# facade.net
KiCad netlist of a schematic drawn in EAGLE
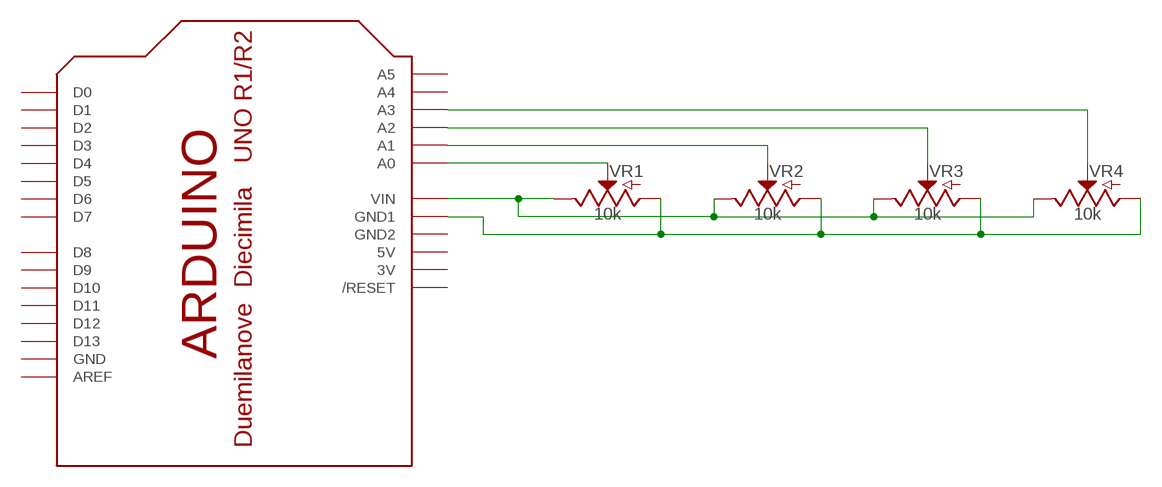
[diagram p0: schematic, sheet 1]

(export (version "E")
  (design (tool "Eeschema 10.0.6"))
  (components
    (comp (ref "U$1")
      (value "ARDUINOUNO")
      (footprint "eagle-import:ARDUINO")
      (libsource (lib "eagle-import") (part "ARDUINOUNO"))
    )
    (comp (ref "VR1")
      (value "10k")
      (footprint "eagle-import:POT-PTH-ALPS")
      (libsource (lib "eagle-import") (part "POTENTIOMETER-PTH-9MM-1/20W-20%"))
    )
    (comp (ref "VR2")
      (value "10k")
      (footprint "eagle-import:POT-PTH-ALPS")
      (libsource (lib "eagle-import") (part "POTENTIOMETER-PTH-9MM-1/20W-20%"))
    )
    (comp (ref "VR3")
      (value "10k")
      (footprint "eagle-import:POT-PTH-ALPS")
      (libsource (lib "eagle-import") (part "POTENTIOMETER-PTH-9MM-1/20W-20%"))
    )
    (comp (ref "VR4")
      (value "10k")
      (footprint "eagle-import:POT-PTH-ALPS")
      (libsource (lib "eagle-import") (part "POTENTIOMETER-PTH-9MM-1/20W-20%"))
    )
  )
  (nets
    (net (code "1") (name "/3V") (class "Default")
      (node (ref "U$1") (pin "3V") (pinfunction "3V_3V") (pintype "power_in"))
    )
    (net (code "2") (name "/5V") (class "Default")
      (node (ref "U$1") (pin "5V") (pinfunction "5V_5V") (pintype "power_in"))
    )
    (net (code "3") (name "/GND") (class "Default")
      (node (ref "U$1") (pin "GND") (pinfunction "GND_GND") (pintype "power_in"))
    )
    (net (code "4") (name "/GND2") (class "Default")
      (node (ref "U$1") (pin "GND2") (pinfunction "GND2_GND2") (pintype "power_in"))
    )
    (net (code "5") (name "Net-(VR1-A)") (class "Default")
      (node (ref "U$1") (pin "GND1") (pinfunction "GND1_GND1") (pintype "power_in"))
      (node (ref "VR1") (pin "P$3") (pinfunction "A_P$3") (pintype "passive"))
      (node (ref "VR2") (pin "P$3") (pinfunction "A_P$3") (pintype "passive"))
      (node (ref "VR3") (pin "P$3") (pinfunction "A_P$3") (pintype "passive"))
      (node (ref "VR4") (pin "P$3") (pinfunction "A_P$3") (pintype "passive"))
    )
    (net (code "6") (name "Net-(VR1-E)") (class "Default")
      (node (ref "U$1") (pin "VIN") (pinfunction "VIN_VIN") (pintype "power_in"))
      (node (ref "VR1") (pin "P$1") (pinfunction "E_P$1") (pintype "passive"))
      (node (ref "VR2") (pin "P$1") (pinfunction "E_P$1") (pintype "passive"))
      (node (ref "VR3") (pin "P$1") (pinfunction "E_P$1") (pintype "passive"))
      (node (ref "VR4") (pin "P$1") (pinfunction "E_P$1") (pintype "passive"))
    )
    (net (code "7") (name "Net-(VR1-S)") (class "Default")
      (node (ref "U$1") (pin "A0") (pinfunction "A0_A0") (pintype "bidirectional"))
      (node (ref "VR1") (pin "P$2") (pinfunction "S_P$2") (pintype "passive"))
    )
    (net (code "8") (name "Net-(VR2-S)") (class "Default")
      (node (ref "U$1") (pin "A1") (pinfunction "A1_A1") (pintype "bidirectional"))
      (node (ref "VR2") (pin "P$2") (pinfunction "S_P$2") (pintype "passive"))
    )
    (net (code "9") (name "Net-(VR3-S)") (class "Default")
      (node (ref "U$1") (pin "A2") (pinfunction "A2_A2") (pintype "bidirectional"))
      (node (ref "VR3") (pin "P$2") (pinfunction "S_P$2") (pintype "passive"))
    )
    (net (code "10") (name "Net-(VR4-S)") (class "Default")
      (node (ref "U$1") (pin "A3") (pinfunction "A3_A3") (pintype "bidirectional"))
      (node (ref "VR4") (pin "P$2") (pinfunction "S_P$2") (pintype "passive"))
    )
    (net (code "11") (name "unconnected-(U$1-PadA4)") (class "Default")
      (node (ref "U$1") (pin "A4") (pinfunction "A4_A4") (pintype "bidirectional"))
    )
    (net (code "12") (name "unconnected-(U$1-PadA5)") (class "Default")
      (node (ref "U$1") (pin "A5") (pinfunction "A5_A5") (pintype "bidirectional"))
    )
    (net (code "13") (name "unconnected-(U$1-PadAREF)") (class "Default")
      (node (ref "U$1") (pin "AREF") (pinfunction "AREF_AREF") (pintype "bidirectional"))
    )
    (net (code "14") (name "unconnected-(U$1-PadD0)") (class "Default")
      (node (ref "U$1") (pin "D0") (pinfunction "D0_D0") (pintype "bidirectional"))
    )
    (net (code "15") (name "unconnected-(U$1-PadD1)") (class "Default")
      (node (ref "U$1") (pin "D1") (pinfunction "D1_D1") (pintype "bidirectional"))
    )
    (net (code "16") (name "unconnected-(U$1-PadD2)") (class "Default")
      (node (ref "U$1") (pin "D2") (pinfunction "D2_D2") (pintype "bidirectional"))
    )
    (net (code "17") (name "unconnected-(U$1-PadD3)") (class "Default")
      (node (ref "U$1") (pin "D3") (pinfunction "D3_D3") (pintype "bidirectional"))
    )
    (net (code "18") (name "unconnected-(U$1-PadD4)") (class "Default")
      (node (ref "U$1") (pin "D4") (pinfunction "D4_D4") (pintype "bidirectional"))
    )
    (net (code "19") (name "unconnected-(U$1-PadD5)") (class "Default")
      (node (ref "U$1") (pin "D5") (pinfunction "D5_D5") (pintype "bidirectional"))
    )
    (net (code "20") (name "unconnected-(U$1-PadD6)") (class "Default")
      (node (ref "U$1") (pin "D6") (pinfunction "D6_D6") (pintype "bidirectional"))
    )
    (net (code "21") (name "unconnected-(U$1-PadD7)") (class "Default")
      (node (ref "U$1") (pin "D7") (pinfunction "D7_D7") (pintype "bidirectional"))
    )
    (net (code "22") (name "unconnected-(U$1-PadD8)") (class "Default")
      (node (ref "U$1") (pin "D8") (pinfunction "D8_D8") (pintype "bidirectional"))
    )
    (net (code "23") (name "unconnected-(U$1-PadD9)") (class "Default")
      (node (ref "U$1") (pin "D9") (pinfunction "D9_D9") (pintype "bidirectional"))
    )
    (net (code "24") (name "unconnected-(U$1-PadD10)") (class "Default")
      (node (ref "U$1") (pin "D10") (pinfunction "D10_D10") (pintype "bidirectional"))
    )
    (net (code "25") (name "unconnected-(U$1-PadD11)") (class "Default")
      (node (ref "U$1") (pin "D11") (pinfunction "D11_D11") (pintype "bidirectional"))
    )
    (net (code "26") (name "unconnected-(U$1-PadD12)") (class "Default")
      (node (ref "U$1") (pin "D12") (pinfunction "D12_D12") (pintype "bidirectional"))
    )
    (net (code "27") (name "unconnected-(U$1-PadD13)") (class "Default")
      (node (ref "U$1") (pin "D13") (pinfunction "D13_D13") (pintype "bidirectional"))
    )
    (net (code "28") (name "unconnected-(U$1-{slash}RESET-PadRESET)") (class "Default")
      (node (ref "U$1") (pin "RESET") (pinfunction "/RESET_RESET") (pintype "bidirectional"))
    )
  )
)
